# Vers_5_Moppy_Board.net
KiCad netlist of a schematic drawn in EAGLE
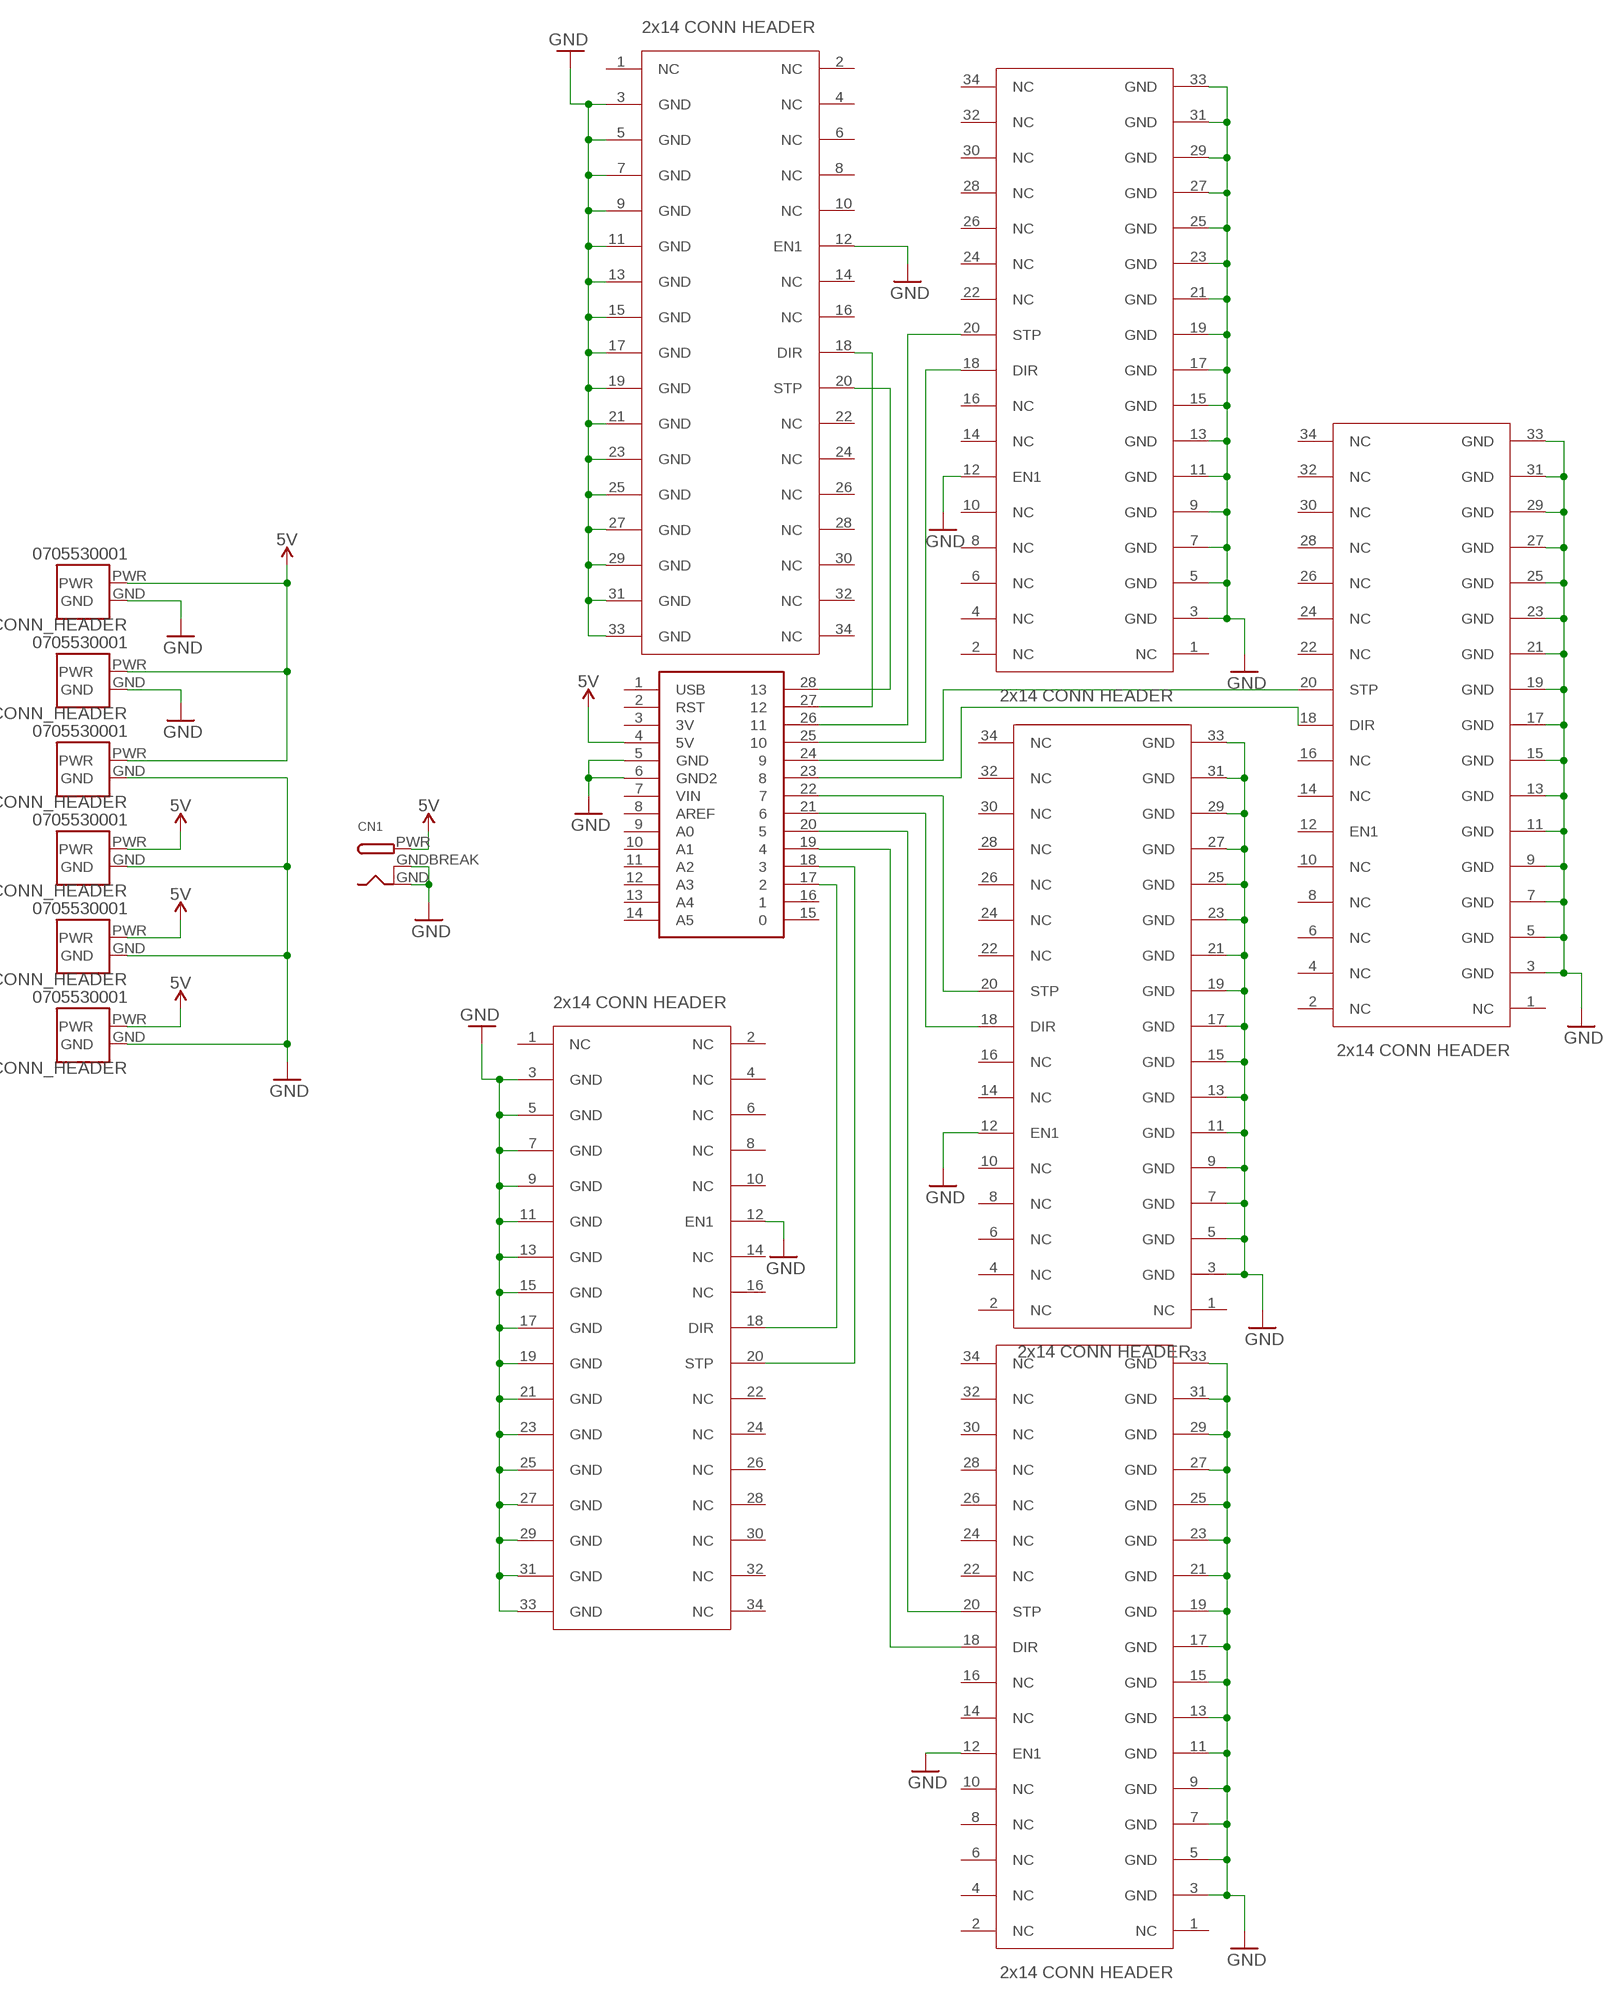
[diagram p0: schematic, sheet 1]

(export (version "E")
  (design (tool "Eeschema 10.0.6"))
  (components
    (comp (ref "CN1")
      (value "DCBARRELPTH")
      (footprint "eagle-import:DCJACK_2MM_PTH")
      (libsource (lib "eagle-import") (part "DCBARRELPTH"))
    )
    (comp (ref "U$1")
      (value "2X14_CONN_HEADER")
      (footprint "eagle-import:2X17_CONN_HEADER")
      (libsource (lib "eagle-import") (part "2X14_CONN_HEADER"))
    )
    (comp (ref "U$2")
      (value "2X14_CONN_HEADER")
      (footprint "eagle-import:2X17_CONN_HEADER")
      (libsource (lib "eagle-import") (part "2X14_CONN_HEADER"))
    )
    (comp (ref "U$3")
      (value "2X14_CONN_HEADER")
      (footprint "eagle-import:2X17_CONN_HEADER")
      (libsource (lib "eagle-import") (part "2X14_CONN_HEADER"))
    )
    (comp (ref "U$4")
      (value "2X14_CONN_HEADER")
      (footprint "eagle-import:2X17_CONN_HEADER")
      (libsource (lib "eagle-import") (part "2X14_CONN_HEADER"))
    )
    (comp (ref "U$5")
      (value "2X14_CONN_HEADER")
      (footprint "eagle-import:2X17_CONN_HEADER")
      (libsource (lib "eagle-import") (part "2X14_CONN_HEADER"))
    )
    (comp (ref "U$6")
      (value "2X14_CONN_HEADER")
      (footprint "eagle-import:2X17_CONN_HEADER")
      (libsource (lib "eagle-import") (part "2X14_CONN_HEADER"))
    )
    (comp (ref "U$8")
      (value "METROMINI")
      (footprint "eagle-import:METROMINI")
      (libsource (lib "eagle-import") (part "METROMINI"))
    )
    (comp (ref "X1")
      (value "0705530001")
      (footprint "eagle-import:MOLEX_0705530001")
      (fields (field (name "DIGI-KEY_PART_NUMBER") "WM4900-ND") (field (name "MF") "Molex"))
      (libsource (lib "eagle-import") (part "0705530001"))
    )
    (comp (ref "X2")
      (value "0705530001")
      (footprint "eagle-import:MOLEX_0705530001")
      (fields (field (name "DIGI-KEY_PART_NUMBER") "WM4900-ND") (field (name "MF") "Molex"))
      (libsource (lib "eagle-import") (part "0705530001"))
    )
    (comp (ref "X3")
      (value "0705530001")
      (footprint "eagle-import:MOLEX_0705530001")
      (fields (field (name "DIGI-KEY_PART_NUMBER") "WM4900-ND") (field (name "MF") "Molex"))
      (libsource (lib "eagle-import") (part "0705530001"))
    )
    (comp (ref "X4")
      (value "0705530001")
      (footprint "eagle-import:MOLEX_0705530001")
      (fields (field (name "DIGI-KEY_PART_NUMBER") "WM4900-ND") (field (name "MF") "Molex"))
      (libsource (lib "eagle-import") (part "0705530001"))
    )
    (comp (ref "X5")
      (value "0705530001")
      (footprint "eagle-import:MOLEX_0705530001")
      (fields (field (name "DIGI-KEY_PART_NUMBER") "WM4900-ND") (field (name "MF") "Molex"))
      (libsource (lib "eagle-import") (part "0705530001"))
    )
    (comp (ref "X6")
      (value "0705530001")
      (footprint "eagle-import:MOLEX_0705530001")
      (fields (field (name "DIGI-KEY_PART_NUMBER") "WM4900-ND") (field (name "MF") "Molex"))
      (libsource (lib "eagle-import") (part "0705530001"))
    )
  )
  (nets
    (net (code "1") (name "5V") (class "Default")
      (node (ref "CN1") (pin "PWR") (pinfunction "PWR_PWR") (pintype "power_in"))
      (node (ref "U$8") (pin "4") (pinfunction "5V_4") (pintype "bidirectional"))
      (node (ref "X1") (pin "PWR") (pinfunction "PWR_PWR") (pintype "passive"))
      (node (ref "X2") (pin "PWR") (pinfunction "PWR_PWR") (pintype "passive"))
      (node (ref "X3") (pin "PWR") (pinfunction "PWR_PWR") (pintype "passive"))
      (node (ref "X4") (pin "PWR") (pinfunction "PWR_PWR") (pintype "passive"))
      (node (ref "X5") (pin "PWR") (pinfunction "PWR_PWR") (pintype "passive"))
      (node (ref "X6") (pin "PWR") (pinfunction "PWR_PWR") (pintype "passive"))
    )
    (net (code "2") (name "GND") (class "Default")
      (node (ref "CN1") (pin "GND") (pinfunction "GND_GND") (pintype "power_in"))
      (node (ref "CN1") (pin "GNDBREAK") (pinfunction "GNDBREAK_GNDBREAK") (pintype "power_in"))
      (node (ref "U$1") (pin "11") (pinfunction "GND_11") (pintype "bidirectional"))
      (node (ref "U$1") (pin "12") (pinfunction "EN1_12") (pintype "bidirectional"))
      (node (ref "U$1") (pin "13") (pinfunction "GND_13") (pintype "bidirectional"))
      (node (ref "U$1") (pin "15") (pinfunction "GND_15") (pintype "bidirectional"))
      (node (ref "U$1") (pin "17") (pinfunction "GND_17") (pintype "bidirectional"))
      (node (ref "U$1") (pin "19") (pinfunction "GND_19") (pintype "bidirectional"))
      (node (ref "U$1") (pin "21") (pinfunction "GND_21") (pintype "bidirectional"))
      (node (ref "U$1") (pin "23") (pinfunction "GND_23") (pintype "bidirectional"))
      (node (ref "U$1") (pin "25") (pinfunction "GND_25") (pintype "bidirectional"))
      (node (ref "U$1") (pin "27") (pinfunction "GND_27") (pintype "bidirectional"))
      (node (ref "U$1") (pin "29") (pinfunction "GND_29") (pintype "bidirectional"))
      (node (ref "U$1") (pin "3") (pinfunction "GND_3") (pintype "bidirectional"))
      (node (ref "U$1") (pin "31") (pinfunction "GND_31") (pintype "bidirectional"))
      (node (ref "U$1") (pin "33") (pinfunction "GND_33") (pintype "bidirectional"))
      (node (ref "U$1") (pin "5") (pinfunction "GND_5") (pintype "bidirectional"))
      (node (ref "U$1") (pin "7") (pinfunction "GND_7") (pintype "bidirectional"))
      (node (ref "U$1") (pin "9") (pinfunction "GND_9") (pintype "bidirectional"))
      (node (ref "U$2") (pin "11") (pinfunction "GND_11") (pintype "bidirectional"))
      (node (ref "U$2") (pin "12") (pinfunction "EN1_12") (pintype "bidirectional"))
      (node (ref "U$2") (pin "13") (pinfunction "GND_13") (pintype "bidirectional"))
      (node (ref "U$2") (pin "15") (pinfunction "GND_15") (pintype "bidirectional"))
      (node (ref "U$2") (pin "17") (pinfunction "GND_17") (pintype "bidirectional"))
      (node (ref "U$2") (pin "19") (pinfunction "GND_19") (pintype "bidirectional"))
      (node (ref "U$2") (pin "21") (pinfunction "GND_21") (pintype "bidirectional"))
      (node (ref "U$2") (pin "23") (pinfunction "GND_23") (pintype "bidirectional"))
      (node (ref "U$2") (pin "25") (pinfunction "GND_25") (pintype "bidirectional"))
      (node (ref "U$2") (pin "27") (pinfunction "GND_27") (pintype "bidirectional"))
      (node (ref "U$2") (pin "29") (pinfunction "GND_29") (pintype "bidirectional"))
      (node (ref "U$2") (pin "3") (pinfunction "GND_3") (pintype "bidirectional"))
      (node (ref "U$2") (pin "31") (pinfunction "GND_31") (pintype "bidirectional"))
      (node (ref "U$2") (pin "33") (pinfunction "GND_33") (pintype "bidirectional"))
      (node (ref "U$2") (pin "5") (pinfunction "GND_5") (pintype "bidirectional"))
      (node (ref "U$2") (pin "7") (pinfunction "GND_7") (pintype "bidirectional"))
      (node (ref "U$2") (pin "9") (pinfunction "GND_9") (pintype "bidirectional"))
      (node (ref "U$3") (pin "11") (pinfunction "GND_11") (pintype "bidirectional"))
      (node (ref "U$3") (pin "12") (pinfunction "EN1_12") (pintype "bidirectional"))
      (node (ref "U$3") (pin "13") (pinfunction "GND_13") (pintype "bidirectional"))
      (node (ref "U$3") (pin "15") (pinfunction "GND_15") (pintype "bidirectional"))
      (node (ref "U$3") (pin "17") (pinfunction "GND_17") (pintype "bidirectional"))
      (node (ref "U$3") (pin "19") (pinfunction "GND_19") (pintype "bidirectional"))
      (node (ref "U$3") (pin "21") (pinfunction "GND_21") (pintype "bidirectional"))
      (node (ref "U$3") (pin "23") (pinfunction "GND_23") (pintype "bidirectional"))
      (node (ref "U$3") (pin "25") (pinfunction "GND_25") (pintype "bidirectional"))
      (node (ref "U$3") (pin "27") (pinfunction "GND_27") (pintype "bidirectional"))
      (node (ref "U$3") (pin "29") (pinfunction "GND_29") (pintype "bidirectional"))
      (node (ref "U$3") (pin "3") (pinfunction "GND_3") (pintype "bidirectional"))
      (node (ref "U$3") (pin "31") (pinfunction "GND_31") (pintype "bidirectional"))
      (node (ref "U$3") (pin "33") (pinfunction "GND_33") (pintype "bidirectional"))
      (node (ref "U$3") (pin "5") (pinfunction "GND_5") (pintype "bidirectional"))
      (node (ref "U$3") (pin "7") (pinfunction "GND_7") (pintype "bidirectional"))
      (node (ref "U$3") (pin "9") (pinfunction "GND_9") (pintype "bidirectional"))
      (node (ref "U$4") (pin "11") (pinfunction "GND_11") (pintype "bidirectional"))
      (node (ref "U$4") (pin "12") (pinfunction "EN1_12") (pintype "bidirectional"))
      (node (ref "U$4") (pin "13") (pinfunction "GND_13") (pintype "bidirectional"))
      (node (ref "U$4") (pin "15") (pinfunction "GND_15") (pintype "bidirectional"))
      (node (ref "U$4") (pin "17") (pinfunction "GND_17") (pintype "bidirectional"))
      (node (ref "U$4") (pin "19") (pinfunction "GND_19") (pintype "bidirectional"))
      (node (ref "U$4") (pin "21") (pinfunction "GND_21") (pintype "bidirectional"))
      (node (ref "U$4") (pin "23") (pinfunction "GND_23") (pintype "bidirectional"))
      (node (ref "U$4") (pin "25") (pinfunction "GND_25") (pintype "bidirectional"))
      (node (ref "U$4") (pin "27") (pinfunction "GND_27") (pintype "bidirectional"))
      (node (ref "U$4") (pin "29") (pinfunction "GND_29") (pintype "bidirectional"))
      (node (ref "U$4") (pin "3") (pinfunction "GND_3") (pintype "bidirectional"))
      (node (ref "U$4") (pin "31") (pinfunction "GND_31") (pintype "bidirectional"))
      (node (ref "U$4") (pin "33") (pinfunction "GND_33") (pintype "bidirectional"))
      (node (ref "U$4") (pin "5") (pinfunction "GND_5") (pintype "bidirectional"))
      (node (ref "U$4") (pin "7") (pinfunction "GND_7") (pintype "bidirectional"))
      (node (ref "U$4") (pin "9") (pinfunction "GND_9") (pintype "bidirectional"))
      (node (ref "U$5") (pin "11") (pinfunction "GND_11") (pintype "bidirectional"))
      (node (ref "U$5") (pin "12") (pinfunction "EN1_12") (pintype "bidirectional"))
      (node (ref "U$5") (pin "13") (pinfunction "GND_13") (pintype "bidirectional"))
      (node (ref "U$5") (pin "15") (pinfunction "GND_15") (pintype "bidirectional"))
      (node (ref "U$5") (pin "17") (pinfunction "GND_17") (pintype "bidirectional"))
      (node (ref "U$5") (pin "19") (pinfunction "GND_19") (pintype "bidirectional"))
      (node (ref "U$5") (pin "21") (pinfunction "GND_21") (pintype "bidirectional"))
      (node (ref "U$5") (pin "23") (pinfunction "GND_23") (pintype "bidirectional"))
      (node (ref "U$5") (pin "25") (pinfunction "GND_25") (pintype "bidirectional"))
      (node (ref "U$5") (pin "27") (pinfunction "GND_27") (pintype "bidirectional"))
      (node (ref "U$5") (pin "29") (pinfunction "GND_29") (pintype "bidirectional"))
      (node (ref "U$5") (pin "3") (pinfunction "GND_3") (pintype "bidirectional"))
      (node (ref "U$5") (pin "31") (pinfunction "GND_31") (pintype "bidirectional"))
      (node (ref "U$5") (pin "33") (pinfunction "GND_33") (pintype "bidirectional"))
      (node (ref "U$5") (pin "5") (pinfunction "GND_5") (pintype "bidirectional"))
      (node (ref "U$5") (pin "7") (pinfunction "GND_7") (pintype "bidirectional"))
      (node (ref "U$5") (pin "9") (pinfunction "GND_9") (pintype "bidirectional"))
      (node (ref "U$6") (pin "11") (pinfunction "GND_11") (pintype "bidirectional"))
      (node (ref "U$6") (pin "13") (pinfunction "GND_13") (pintype "bidirectional"))
      (node (ref "U$6") (pin "15") (pinfunction "GND_15") (pintype "bidirectional"))
      (node (ref "U$6") (pin "17") (pinfunction "GND_17") (pintype "bidirectional"))
      (node (ref "U$6") (pin "19") (pinfunction "GND_19") (pintype "bidirectional"))
      (node (ref "U$6") (pin "21") (pinfunction "GND_21") (pintype "bidirectional"))
      (node (ref "U$6") (pin "23") (pinfunction "GND_23") (pintype "bidirectional"))
      (node (ref "U$6") (pin "25") (pinfunction "GND_25") (pintype "bidirectional"))
      (node (ref "U$6") (pin "27") (pinfunction "GND_27") (pintype "bidirectional"))
      (node (ref "U$6") (pin "29") (pinfunction "GND_29") (pintype "bidirectional"))
      (node (ref "U$6") (pin "3") (pinfunction "GND_3") (pintype "bidirectional"))
      (node (ref "U$6") (pin "31") (pinfunction "GND_31") (pintype "bidirectional"))
      (node (ref "U$6") (pin "33") (pinfunction "GND_33") (pintype "bidirectional"))
      (node (ref "U$6") (pin "5") (pinfunction "GND_5") (pintype "bidirectional"))
      (node (ref "U$6") (pin "7") (pinfunction "GND_7") (pintype "bidirectional"))
      (node (ref "U$6") (pin "9") (pinfunction "GND_9") (pintype "bidirectional"))
      (node (ref "U$8") (pin "5") (pinfunction "GND_5") (pintype "bidirectional"))
      (node (ref "U$8") (pin "6") (pinfunction "GND2_6") (pintype "bidirectional"))
      (node (ref "X1") (pin "GND") (pinfunction "GND_GND") (pintype "passive"))
      (node (ref "X2") (pin "GND") (pinfunction "GND_GND") (pintype "passive"))
      (node (ref "X3") (pin "GND") (pinfunction "GND_GND") (pintype "passive"))
      (node (ref "X4") (pin "GND") (pinfunction "GND_GND") (pintype "passive"))
      (node (ref "X5") (pin "GND") (pinfunction "GND_GND") (pintype "passive"))
      (node (ref "X6") (pin "GND") (pinfunction "GND_GND") (pintype "passive"))
    )
    (net (code "3") (name "Net-(U$1-DIR)") (class "Default")
      (node (ref "U$1") (pin "18") (pinfunction "DIR_18") (pintype "bidirectional"))
      (node (ref "U$8") (pin "17") (pinfunction "2_17") (pintype "bidirectional"))
    )
    (net (code "4") (name "Net-(U$1-STP)") (class "Default")
      (node (ref "U$1") (pin "20") (pinfunction "STP_20") (pintype "bidirectional"))
      (node (ref "U$8") (pin "18") (pinfunction "3_18") (pintype "bidirectional"))
    )
    (net (code "5") (name "Net-(U$2-DIR)") (class "Default")
      (node (ref "U$2") (pin "18") (pinfunction "DIR_18") (pintype "bidirectional"))
      (node (ref "U$8") (pin "27") (pinfunction "12_27") (pintype "bidirectional"))
    )
    (net (code "6") (name "Net-(U$2-STP)") (class "Default")
      (node (ref "U$2") (pin "20") (pinfunction "STP_20") (pintype "bidirectional"))
      (node (ref "U$8") (pin "28") (pinfunction "13_28") (pintype "bidirectional"))
    )
    (net (code "7") (name "Net-(U$3-DIR)") (class "Default")
      (node (ref "U$3") (pin "18") (pinfunction "DIR_18") (pintype "bidirectional"))
      (node (ref "U$8") (pin "25") (pinfunction "10_25") (pintype "bidirectional"))
    )
    (net (code "8") (name "Net-(U$3-STP)") (class "Default")
      (node (ref "U$3") (pin "20") (pinfunction "STP_20") (pintype "bidirectional"))
      (node (ref "U$8") (pin "26") (pinfunction "11_26") (pintype "bidirectional"))
    )
    (net (code "9") (name "Net-(U$4-DIR)") (class "Default")
      (node (ref "U$4") (pin "18") (pinfunction "DIR_18") (pintype "bidirectional"))
      (node (ref "U$8") (pin "19") (pinfunction "4_19") (pintype "bidirectional"))
    )
    (net (code "10") (name "Net-(U$4-STP)") (class "Default")
      (node (ref "U$4") (pin "20") (pinfunction "STP_20") (pintype "bidirectional"))
      (node (ref "U$8") (pin "20") (pinfunction "5_20") (pintype "bidirectional"))
    )
    (net (code "11") (name "Net-(U$5-DIR)") (class "Default")
      (node (ref "U$5") (pin "18") (pinfunction "DIR_18") (pintype "bidirectional"))
      (node (ref "U$8") (pin "21") (pinfunction "6_21") (pintype "bidirectional"))
    )
    (net (code "12") (name "Net-(U$5-STP)") (class "Default")
      (node (ref "U$5") (pin "20") (pinfunction "STP_20") (pintype "bidirectional"))
      (node (ref "U$8") (pin "22") (pinfunction "7_22") (pintype "bidirectional"))
    )
    (net (code "13") (name "Net-(U$6-DIR)") (class "Default")
      (node (ref "U$6") (pin "18") (pinfunction "DIR_18") (pintype "bidirectional"))
      (node (ref "U$8") (pin "23") (pinfunction "8_23") (pintype "bidirectional"))
    )
    (net (code "14") (name "Net-(U$6-STP)") (class "Default")
      (node (ref "U$6") (pin "20") (pinfunction "STP_20") (pintype "bidirectional"))
      (node (ref "U$8") (pin "24") (pinfunction "9_24") (pintype "bidirectional"))
    )
    (net (code "15") (name "unconnected-(U$1-NC-Pad1)") (class "Default")
      (node (ref "U$1") (pin "1") (pinfunction "NC_1") (pintype "bidirectional"))
    )
    (net (code "16") (name "unconnected-(U$1-NC-Pad2)") (class "Default")
      (node (ref "U$1") (pin "2") (pinfunction "NC_2") (pintype "bidirectional"))
    )
    (net (code "17") (name "unconnected-(U$1-NC-Pad4)") (class "Default")
      (node (ref "U$1") (pin "4") (pinfunction "NC_4") (pintype "bidirectional"))
    )
    (net (code "18") (name "unconnected-(U$1-NC-Pad6)") (class "Default")
      (node (ref "U$1") (pin "6") (pinfunction "NC_6") (pintype "bidirectional"))
    )
    (net (code "19") (name "unconnected-(U$1-NC-Pad8)") (class "Default")
      (node (ref "U$1") (pin "8") (pinfunction "NC_8") (pintype "bidirectional"))
    )
    (net (code "20") (name "unconnected-(U$1-NC-Pad10)") (class "Default")
      (node (ref "U$1") (pin "10") (pinfunction "NC_10") (pintype "bidirectional"))
    )
    (net (code "21") (name "unconnected-(U$1-NC-Pad14)") (class "Default")
      (node (ref "U$1") (pin "14") (pinfunction "NC_14") (pintype "bidirectional"))
    )
    (net (code "22") (name "unconnected-(U$1-NC-Pad16)") (class "Default")
      (node (ref "U$1") (pin "16") (pinfunction "NC_16") (pintype "bidirectional"))
    )
    (net (code "23") (name "unconnected-(U$1-NC-Pad22)") (class "Default")
      (node (ref "U$1") (pin "22") (pinfunction "NC_22") (pintype "bidirectional"))
    )
    (net (code "24") (name "unconnected-(U$1-NC-Pad24)") (class "Default")
      (node (ref "U$1") (pin "24") (pinfunction "NC_24") (pintype "bidirectional"))
    )
    (net (code "25") (name "unconnected-(U$1-NC-Pad26)") (class "Default")
      (node (ref "U$1") (pin "26") (pinfunction "NC_26") (pintype "bidirectional"))
    )
    (net (code "26") (name "unconnected-(U$1-NC-Pad28)") (class "Default")
      (node (ref "U$1") (pin "28") (pinfunction "NC_28") (pintype "bidirectional"))
    )
    (net (code "27") (name "unconnected-(U$1-NC-Pad30)") (class "Default")
      (node (ref "U$1") (pin "30") (pinfunction "NC_30") (pintype "bidirectional"))
    )
    (net (code "28") (name "unconnected-(U$1-NC-Pad32)") (class "Default")
      (node (ref "U$1") (pin "32") (pinfunction "NC_32") (pintype "bidirectional"))
    )
    (net (code "29") (name "unconnected-(U$1-NC-Pad34)") (class "Default")
      (node (ref "U$1") (pin "34") (pinfunction "NC_34") (pintype "bidirectional"))
    )
    (net (code "30") (name "unconnected-(U$2-NC-Pad1)") (class "Default")
      (node (ref "U$2") (pin "1") (pinfunction "NC_1") (pintype "bidirectional"))
    )
    (net (code "31") (name "unconnected-(U$2-NC-Pad2)") (class "Default")
      (node (ref "U$2") (pin "2") (pinfunction "NC_2") (pintype "bidirectional"))
    )
    (net (code "32") (name "unconnected-(U$2-NC-Pad4)") (class "Default")
      (node (ref "U$2") (pin "4") (pinfunction "NC_4") (pintype "bidirectional"))
    )
    (net (code "33") (name "unconnected-(U$2-NC-Pad6)") (class "Default")
      (node (ref "U$2") (pin "6") (pinfunction "NC_6") (pintype "bidirectional"))
    )
    (net (code "34") (name "unconnected-(U$2-NC-Pad8)") (class "Default")
      (node (ref "U$2") (pin "8") (pinfunction "NC_8") (pintype "bidirectional"))
    )
    (net (code "35") (name "unconnected-(U$2-NC-Pad10)") (class "Default")
      (node (ref "U$2") (pin "10") (pinfunction "NC_10") (pintype "bidirectional"))
    )
    (net (code "36") (name "unconnected-(U$2-NC-Pad14)") (class "Default")
      (node (ref "U$2") (pin "14") (pinfunction "NC_14") (pintype "bidirectional"))
    )
    (net (code "37") (name "unconnected-(U$2-NC-Pad16)") (class "Default")
      (node (ref "U$2") (pin "16") (pinfunction "NC_16") (pintype "bidirectional"))
    )
    (net (code "38") (name "unconnected-(U$2-NC-Pad22)") (class "Default")
      (node (ref "U$2") (pin "22") (pinfunction "NC_22") (pintype "bidirectional"))
    )
    (net (code "39") (name "unconnected-(U$2-NC-Pad24)") (class "Default")
      (node (ref "U$2") (pin "24") (pinfunction "NC_24") (pintype "bidirectional"))
    )
    (net (code "40") (name "unconnected-(U$2-NC-Pad26)") (class "Default")
      (node (ref "U$2") (pin "26") (pinfunction "NC_26") (pintype "bidirectional"))
    )
    (net (code "41") (name "unconnected-(U$2-NC-Pad28)") (class "Default")
      (node (ref "U$2") (pin "28") (pinfunction "NC_28") (pintype "bidirectional"))
    )
    (net (code "42") (name "unconnected-(U$2-NC-Pad30)") (class "Default")
      (node (ref "U$2") (pin "30") (pinfunction "NC_30") (pintype "bidirectional"))
    )
    (net (code "43") (name "unconnected-(U$2-NC-Pad32)") (class "Default")
      (node (ref "U$2") (pin "32") (pinfunction "NC_32") (pintype "bidirectional"))
    )
    (net (code "44") (name "unconnected-(U$2-NC-Pad34)") (class "Default")
      (node (ref "U$2") (pin "34") (pinfunction "NC_34") (pintype "bidirectional"))
    )
    (net (code "45") (name "unconnected-(U$3-NC-Pad1)") (class "Default")
      (node (ref "U$3") (pin "1") (pinfunction "NC_1") (pintype "bidirectional"))
    )
    (net (code "46") (name "unconnected-(U$3-NC-Pad2)") (class "Default")
      (node (ref "U$3") (pin "2") (pinfunction "NC_2") (pintype "bidirectional"))
    )
    (net (code "47") (name "unconnected-(U$3-NC-Pad4)") (class "Default")
      (node (ref "U$3") (pin "4") (pinfunction "NC_4") (pintype "bidirectional"))
    )
    (net (code "48") (name "unconnected-(U$3-NC-Pad6)") (class "Default")
      (node (ref "U$3") (pin "6") (pinfunction "NC_6") (pintype "bidirectional"))
    )
    (net (code "49") (name "unconnected-(U$3-NC-Pad8)") (class "Default")
      (node (ref "U$3") (pin "8") (pinfunction "NC_8") (pintype "bidirectional"))
    )
    (net (code "50") (name "unconnected-(U$3-NC-Pad10)") (class "Default")
      (node (ref "U$3") (pin "10") (pinfunction "NC_10") (pintype "bidirectional"))
    )
    (net (code "51") (name "unconnected-(U$3-NC-Pad14)") (class "Default")
      (node (ref "U$3") (pin "14") (pinfunction "NC_14") (pintype "bidirectional"))
    )
    (net (code "52") (name "unconnected-(U$3-NC-Pad16)") (class "Default")
      (node (ref "U$3") (pin "16") (pinfunction "NC_16") (pintype "bidirectional"))
    )
    (net (code "53") (name "unconnected-(U$3-NC-Pad22)") (class "Default")
      (node (ref "U$3") (pin "22") (pinfunction "NC_22") (pintype "bidirectional"))
    )
    (net (code "54") (name "unconnected-(U$3-NC-Pad24)") (class "Default")
      (node (ref "U$3") (pin "24") (pinfunction "NC_24") (pintype "bidirectional"))
    )
    (net (code "55") (name "unconnected-(U$3-NC-Pad26)") (class "Default")
      (node (ref "U$3") (pin "26") (pinfunction "NC_26") (pintype "bidirectional"))
    )
    (net (code "56") (name "unconnected-(U$3-NC-Pad28)") (class "Default")
      (node (ref "U$3") (pin "28") (pinfunction "NC_28") (pintype "bidirectional"))
    )
    (net (code "57") (name "unconnected-(U$3-NC-Pad30)") (class "Default")
      (node (ref "U$3") (pin "30") (pinfunction "NC_30") (pintype "bidirectional"))
    )
    (net (code "58") (name "unconnected-(U$3-NC-Pad32)") (class "Default")
      (node (ref "U$3") (pin "32") (pinfunction "NC_32") (pintype "bidirectional"))
    )
    (net (code "59") (name "unconnected-(U$3-NC-Pad34)") (class "Default")
      (node (ref "U$3") (pin "34") (pinfunction "NC_34") (pintype "bidirectional"))
    )
    (net (code "60") (name "unconnected-(U$4-NC-Pad1)") (class "Default")
      (node (ref "U$4") (pin "1") (pinfunction "NC_1") (pintype "bidirectional"))
    )
    (net (code "61") (name "unconnected-(U$4-NC-Pad2)") (class "Default")
      (node (ref "U$4") (pin "2") (pinfunction "NC_2") (pintype "bidirectional"))
    )
    (net (code "62") (name "unconnected-(U$4-NC-Pad4)") (class "Default")
      (node (ref "U$4") (pin "4") (pinfunction "NC_4") (pintype "bidirectional"))
    )
    (net (code "63") (name "unconnected-(U$4-NC-Pad6)") (class "Default")
      (node (ref "U$4") (pin "6") (pinfunction "NC_6") (pintype "bidirectional"))
    )
    (net (code "64") (name "unconnected-(U$4-NC-Pad8)") (class "Default")
      (node (ref "U$4") (pin "8") (pinfunction "NC_8") (pintype "bidirectional"))
    )
    (net (code "65") (name "unconnected-(U$4-NC-Pad10)") (class "Default")
      (node (ref "U$4") (pin "10") (pinfunction "NC_10") (pintype "bidirectional"))
    )
    (net (code "66") (name "unconnected-(U$4-NC-Pad14)") (class "Default")
      (node (ref "U$4") (pin "14") (pinfunction "NC_14") (pintype "bidirectional"))
    )
    (net (code "67") (name "unconnected-(U$4-NC-Pad16)") (class "Default")
      (node (ref "U$4") (pin "16") (pinfunction "NC_16") (pintype "bidirectional"))
    )
    (net (code "68") (name "unconnected-(U$4-NC-Pad22)") (class "Default")
      (node (ref "U$4") (pin "22") (pinfunction "NC_22") (pintype "bidirectional"))
    )
    (net (code "69") (name "unconnected-(U$4-NC-Pad24)") (class "Default")
      (node (ref "U$4") (pin "24") (pinfunction "NC_24") (pintype "bidirectional"))
    )
    (net (code "70") (name "unconnected-(U$4-NC-Pad26)") (class "Default")
      (node (ref "U$4") (pin "26") (pinfunction "NC_26") (pintype "bidirectional"))
    )
    (net (code "71") (name "unconnected-(U$4-NC-Pad28)") (class "Default")
      (node (ref "U$4") (pin "28") (pinfunction "NC_28") (pintype "bidirectional"))
    )
    (net (code "72") (name "unconnected-(U$4-NC-Pad30)") (class "Default")
      (node (ref "U$4") (pin "30") (pinfunction "NC_30") (pintype "bidirectional"))
    )
    (net (code "73") (name "unconnected-(U$4-NC-Pad32)") (class "Default")
      (node (ref "U$4") (pin "32") (pinfunction "NC_32") (pintype "bidirectional"))
    )
    (net (code "74") (name "unconnected-(U$4-NC-Pad34)") (class "Default")
      (node (ref "U$4") (pin "34") (pinfunction "NC_34") (pintype "bidirectional"))
    )
    (net (code "75") (name "unconnected-(U$5-NC-Pad1)") (class "Default")
      (node (ref "U$5") (pin "1") (pinfunction "NC_1") (pintype "bidirectional"))
    )
    (net (code "76") (name "unconnected-(U$5-NC-Pad2)") (class "Default")
      (node (ref "U$5") (pin "2") (pinfunction "NC_2") (pintype "bidirectional"))
    )
    (net (code "77") (name "unconnected-(U$5-NC-Pad4)") (class "Default")
      (node (ref "U$5") (pin "4") (pinfunction "NC_4") (pintype "bidirectional"))
    )
    (net (code "78") (name "unconnected-(U$5-NC-Pad6)") (class "Default")
      (node (ref "U$5") (pin "6") (pinfunction "NC_6") (pintype "bidirectional"))
    )
    (net (code "79") (name "unconnected-(U$5-NC-Pad8)") (class "Default")
      (node (ref "U$5") (pin "8") (pinfunction "NC_8") (pintype "bidirectional"))
    )
    (net (code "80") (name "unconnected-(U$5-NC-Pad10)") (class "Default")
      (node (ref "U$5") (pin "10") (pinfunction "NC_10") (pintype "bidirectional"))
    )
    (net (code "81") (name "unconnected-(U$5-NC-Pad14)") (class "Default")
      (node (ref "U$5") (pin "14") (pinfunction "NC_14") (pintype "bidirectional"))
    )
    (net (code "82") (name "unconnected-(U$5-NC-Pad16)") (class "Default")
      (node (ref "U$5") (pin "16") (pinfunction "NC_16") (pintype "bidirectional"))
    )
    (net (code "83") (name "unconnected-(U$5-NC-Pad22)") (class "Default")
      (node (ref "U$5") (pin "22") (pinfunction "NC_22") (pintype "bidirectional"))
    )
    (net (code "84") (name "unconnected-(U$5-NC-Pad24)") (class "Default")
      (node (ref "U$5") (pin "24") (pinfunction "NC_24") (pintype "bidirectional"))
    )
    (net (code "85") (name "unconnected-(U$5-NC-Pad26)") (class "Default")
      (node (ref "U$5") (pin "26") (pinfunction "NC_26") (pintype "bidirectional"))
    )
    (net (code "86") (name "unconnected-(U$5-NC-Pad28)") (class "Default")
      (node (ref "U$5") (pin "28") (pinfunction "NC_28") (pintype "bidirectional"))
    )
    (net (code "87") (name "unconnected-(U$5-NC-Pad30)") (class "Default")
      (node (ref "U$5") (pin "30") (pinfunction "NC_30") (pintype "bidirectional"))
    )
    (net (code "88") (name "unconnected-(U$5-NC-Pad32)") (class "Default")
      (node (ref "U$5") (pin "32") (pinfunction "NC_32") (pintype "bidirectional"))
    )
    (net (code "89") (name "unconnected-(U$5-NC-Pad34)") (class "Default")
      (node (ref "U$5") (pin "34") (pinfunction "NC_34") (pintype "bidirectional"))
    )
    (net (code "90") (name "unconnected-(U$6-EN1-Pad12)") (class "Default")
      (node (ref "U$6") (pin "12") (pinfunction "EN1_12") (pintype "bidirectional"))
    )
    (net (code "91") (name "unconnected-(U$6-NC-Pad1)") (class "Default")
      (node (ref "U$6") (pin "1") (pinfunction "NC_1") (pintype "bidirectional"))
    )
    (net (code "92") (name "unconnected-(U$6-NC-Pad2)") (class "Default")
      (node (ref "U$6") (pin "2") (pinfunction "NC_2") (pintype "bidirectional"))
    )
    (net (code "93") (name "unconnected-(U$6-NC-Pad4)") (class "Default")
      (node (ref "U$6") (pin "4") (pinfunction "NC_4") (pintype "bidirectional"))
    )
    (net (code "94") (name "unconnected-(U$6-NC-Pad6)") (class "Default")
      (node (ref "U$6") (pin "6") (pinfunction "NC_6") (pintype "bidirectional"))
    )
    (net (code "95") (name "unconnected-(U$6-NC-Pad8)") (class "Default")
      (node (ref "U$6") (pin "8") (pinfunction "NC_8") (pintype "bidirectional"))
    )
    (net (code "96") (name "unconnected-(U$6-NC-Pad10)") (class "Default")
      (node (ref "U$6") (pin "10") (pinfunction "NC_10") (pintype "bidirectional"))
    )
    (net (code "97") (name "unconnected-(U$6-NC-Pad14)") (class "Default")
      (node (ref "U$6") (pin "14") (pinfunction "NC_14") (pintype "bidirectional"))
    )
    (net (code "98") (name "unconnected-(U$6-NC-Pad16)") (class "Default")
      (node (ref "U$6") (pin "16") (pinfunction "NC_16") (pintype "bidirectional"))
    )
    (net (code "99") (name "unconnected-(U$6-NC-Pad22)") (class "Default")
      (node (ref "U$6") (pin "22") (pinfunction "NC_22") (pintype "bidirectional"))
    )
    (net (code "100") (name "unconnected-(U$6-NC-Pad24)") (class "Default")
      (node (ref "U$6") (pin "24") (pinfunction "NC_24") (pintype "bidirectional"))
    )
    (net (code "101") (name "unconnected-(U$6-NC-Pad26)") (class "Default")
      (node (ref "U$6") (pin "26") (pinfunction "NC_26") (pintype "bidirectional"))
    )
    (net (code "102") (name "unconnected-(U$6-NC-Pad28)") (class "Default")
      (node (ref "U$6") (pin "28") (pinfunction "NC_28") (pintype "bidirectional"))
    )
    (net (code "103") (name "unconnected-(U$6-NC-Pad30)") (class "Default")
      (node (ref "U$6") (pin "30") (pinfunction "NC_30") (pintype "bidirectional"))
    )
    (net (code "104") (name "unconnected-(U$6-NC-Pad32)") (class "Default")
      (node (ref "U$6") (pin "32") (pinfunction "NC_32") (pintype "bidirectional"))
    )
    (net (code "105") (name "unconnected-(U$6-NC-Pad34)") (class "Default")
      (node (ref "U$6") (pin "34") (pinfunction "NC_34") (pintype "bidirectional"))
    )
    (net (code "106") (name "unconnected-(U$8-0-Pad15)") (class "Default")
      (node (ref "U$8") (pin "15") (pinfunction "0_15") (pintype "bidirectional"))
    )
    (net (code "107") (name "unconnected-(U$8-1-Pad16)") (class "Default")
      (node (ref "U$8") (pin "16") (pinfunction "1_16") (pintype "bidirectional"))
    )
    (net (code "108") (name "unconnected-(U$8-3V-Pad3)") (class "Default")
      (node (ref "U$8") (pin "3") (pinfunction "3V_3") (pintype "bidirectional"))
    )
    (net (code "109") (name "unconnected-(U$8-A0-Pad9)") (class "Default")
      (node (ref "U$8") (pin "9") (pinfunction "A0_9") (pintype "bidirectional"))
    )
    (net (code "110") (name "unconnected-(U$8-A1-Pad10)") (class "Default")
      (node (ref "U$8") (pin "10") (pinfunction "A1_10") (pintype "bidirectional"))
    )
    (net (code "111") (name "unconnected-(U$8-A2-Pad11)") (class "Default")
      (node (ref "U$8") (pin "11") (pinfunction "A2_11") (pintype "bidirectional"))
    )
    (net (code "112") (name "unconnected-(U$8-A3-Pad12)") (class "Default")
      (node (ref "U$8") (pin "12") (pinfunction "A3_12") (pintype "bidirectional"))
    )
    (net (code "113") (name "unconnected-(U$8-A4-Pad13)") (class "Default")
      (node (ref "U$8") (pin "13") (pinfunction "A4_13") (pintype "bidirectional"))
    )
    (net (code "114") (name "unconnected-(U$8-A5-Pad14)") (class "Default")
      (node (ref "U$8") (pin "14") (pinfunction "A5_14") (pintype "bidirectional"))
    )
    (net (code "115") (name "unconnected-(U$8-AREF-Pad8)") (class "Default")
      (node (ref "U$8") (pin "8") (pinfunction "AREF_8") (pintype "bidirectional"))
    )
    (net (code "116") (name "unconnected-(U$8-RST-Pad2)") (class "Default")
      (node (ref "U$8") (pin "2") (pinfunction "RST_2") (pintype "bidirectional"))
    )
    (net (code "117") (name "unconnected-(U$8-USB-Pad1)") (class "Default")
      (node (ref "U$8") (pin "1") (pinfunction "USB_1") (pintype "bidirectional"))
    )
    (net (code "118") (name "unconnected-(U$8-VIN-Pad7)") (class "Default")
      (node (ref "U$8") (pin "7") (pinfunction "VIN_7") (pintype "bidirectional"))
    )
  )
)
